# LED.net
KiCad netlist of a schematic drawn in Altium Designer
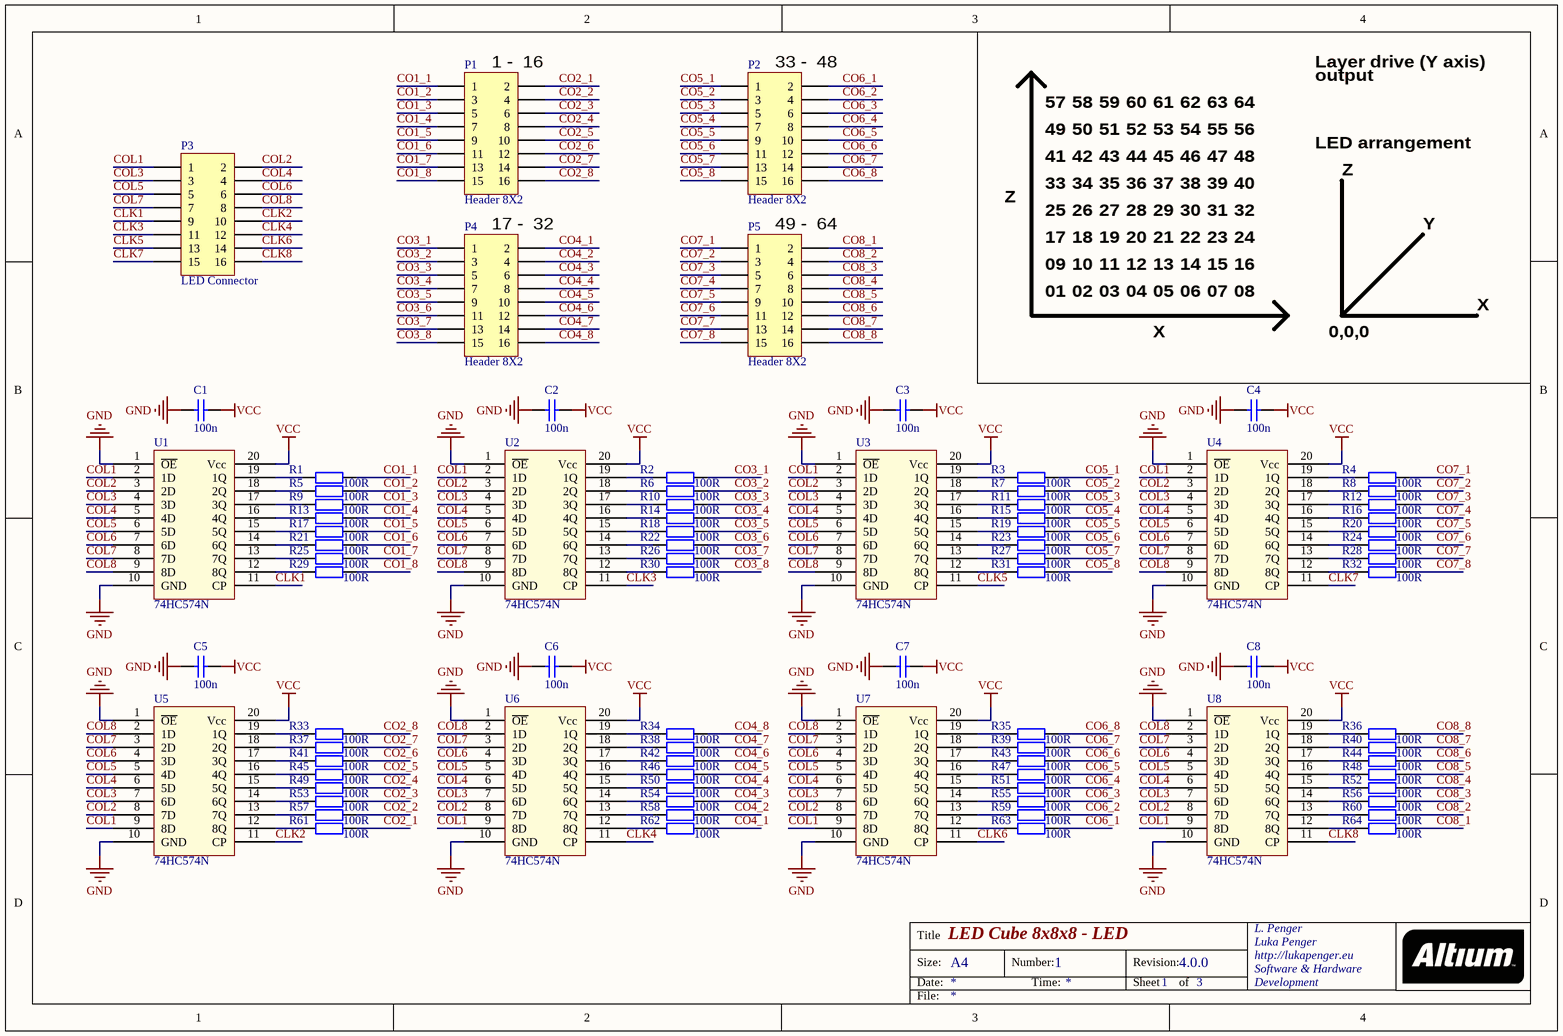
[diagram p0: LED.SchDoc]

(export (version "E")
  (design (tool "Eeschema 10.0.6"))
  (components
    (comp (ref "C1")
      (value "100n")
      (footprint "1608[0603]")
      (description "Capacitor")
      (fields (field (name "PUBLISHER") "Altium Limited"))
      (libsource (lib "Miscellaneous Devices") (part "Cap"))
    )
    (comp (ref "C2")
      (value "100n")
      (footprint "1608[0603]")
      (description "Capacitor")
      (fields (field (name "PUBLISHER") "Altium Limited"))
      (libsource (lib "Miscellaneous Devices") (part "Cap"))
    )
    (comp (ref "C3")
      (value "100n")
      (footprint "1608[0603]")
      (description "Capacitor")
      (fields (field (name "PUBLISHER") "Altium Limited"))
      (libsource (lib "Miscellaneous Devices") (part "Cap"))
    )
    (comp (ref "C4")
      (value "100n")
      (footprint "1608[0603]")
      (description "Capacitor")
      (fields (field (name "PUBLISHER") "Altium Limited"))
      (libsource (lib "Miscellaneous Devices") (part "Cap"))
    )
    (comp (ref "C5")
      (value "100n")
      (footprint "1608[0603]")
      (description "Capacitor")
      (fields (field (name "PUBLISHER") "Altium Limited"))
      (libsource (lib "Miscellaneous Devices") (part "Cap"))
    )
    (comp (ref "C6")
      (value "100n")
      (footprint "1608[0603]")
      (description "Capacitor")
      (fields (field (name "PUBLISHER") "Altium Limited"))
      (libsource (lib "Miscellaneous Devices") (part "Cap"))
    )
    (comp (ref "C7")
      (value "100n")
      (footprint "1608[0603]")
      (description "Capacitor")
      (fields (field (name "PUBLISHER") "Altium Limited"))
      (libsource (lib "Miscellaneous Devices") (part "Cap"))
    )
    (comp (ref "C8")
      (value "100n")
      (footprint "1608[0603]")
      (description "Capacitor")
      (fields (field (name "PUBLISHER") "Altium Limited"))
      (libsource (lib "Miscellaneous Devices") (part "Cap"))
    )
    (comp (ref "P1")
      (value "Header 8X2")
      (footprint "IDC-2x8")
      (description "Header, 8-Pin, Dual row")
      (fields (field (name "PUBLISHER") "Altium Limited"))
      (libsource (lib "Miscellaneous Connectors") (part "Header 8X2"))
    )
    (comp (ref "P2")
      (value "Header 8X2")
      (footprint "IDC-2x8")
      (description "Header, 8-Pin, Dual row")
      (fields (field (name "PUBLISHER") "Altium Limited"))
      (libsource (lib "Miscellaneous Connectors") (part "Header 8X2"))
    )
    (comp (ref "P3")
      (value "LED Connector")
      (footprint "IDC-2x8")
      (description "Header, 8-Pin, Dual row")
      (fields (field (name "PUBLISHER") "Altium Limited"))
      (libsource (lib "Miscellaneous Connectors") (part "Header 8X2"))
    )
    (comp (ref "P4")
      (value "Header 8X2")
      (footprint "IDC-2x8")
      (description "Header, 8-Pin, Dual row")
      (fields (field (name "PUBLISHER") "Altium Limited"))
      (libsource (lib "Miscellaneous Connectors") (part "Header 8X2"))
    )
    (comp (ref "P5")
      (value "Header 8X2")
      (footprint "IDC-2x8")
      (description "Header, 8-Pin, Dual row")
      (fields (field (name "PUBLISHER") "Altium Limited"))
      (libsource (lib "Miscellaneous Connectors") (part "Header 8X2"))
    )
    (comp (ref "R1")
      (value "100R")
      (footprint "C1206")
      (description "Resistor")
      (fields (field (name "PUBLISHER") "Altium Limited"))
      (libsource (lib "Miscellaneous Devices") (part "Res2"))
    )
    (comp (ref "R2")
      (value "100R")
      (footprint "C1206")
      (description "Resistor")
      (fields (field (name "PUBLISHER") "Altium Limited"))
      (libsource (lib "Miscellaneous Devices") (part "Res2"))
    )
    (comp (ref "R3")
      (value "100R")
      (footprint "C1206")
      (description "Resistor")
      (fields (field (name "PUBLISHER") "Altium Limited"))
      (libsource (lib "Miscellaneous Devices") (part "Res2"))
    )
    (comp (ref "R4")
      (value "100R")
      (footprint "C1206")
      (description "Resistor")
      (fields (field (name "PUBLISHER") "Altium Limited"))
      (libsource (lib "Miscellaneous Devices") (part "Res2"))
    )
    (comp (ref "R5")
      (value "100R")
      (footprint "C1206")
      (description "Resistor")
      (fields (field (name "PUBLISHER") "Altium Limited"))
      (libsource (lib "Miscellaneous Devices") (part "Res2"))
    )
    (comp (ref "R6")
      (value "100R")
      (footprint "C1206")
      (description "Resistor")
      (fields (field (name "PUBLISHER") "Altium Limited"))
      (libsource (lib "Miscellaneous Devices") (part "Res2"))
    )
    (comp (ref "R7")
      (value "100R")
      (footprint "C1206")
      (description "Resistor")
      (fields (field (name "PUBLISHER") "Altium Limited"))
      (libsource (lib "Miscellaneous Devices") (part "Res2"))
    )
    (comp (ref "R8")
      (value "100R")
      (footprint "C1206")
      (description "Resistor")
      (fields (field (name "PUBLISHER") "Altium Limited"))
      (libsource (lib "Miscellaneous Devices") (part "Res2"))
    )
    (comp (ref "R9")
      (value "100R")
      (footprint "C1206")
      (description "Resistor")
      (fields (field (name "PUBLISHER") "Altium Limited"))
      (libsource (lib "Miscellaneous Devices") (part "Res2"))
    )
    (comp (ref "R10")
      (value "100R")
      (footprint "C1206")
      (description "Resistor")
      (fields (field (name "PUBLISHER") "Altium Limited"))
      (libsource (lib "Miscellaneous Devices") (part "Res2"))
    )
    (comp (ref "R11")
      (value "100R")
      (footprint "C1206")
      (description "Resistor")
      (fields (field (name "PUBLISHER") "Altium Limited"))
      (libsource (lib "Miscellaneous Devices") (part "Res2"))
    )
    (comp (ref "R12")
      (value "100R")
      (footprint "C1206")
      (description "Resistor")
      (fields (field (name "PUBLISHER") "Altium Limited"))
      (libsource (lib "Miscellaneous Devices") (part "Res2"))
    )
    (comp (ref "R13")
      (value "100R")
      (footprint "C1206")
      (description "Resistor")
      (fields (field (name "PUBLISHER") "Altium Limited"))
      (libsource (lib "Miscellaneous Devices") (part "Res2"))
    )
    (comp (ref "R14")
      (value "100R")
      (footprint "C1206")
      (description "Resistor")
      (fields (field (name "PUBLISHER") "Altium Limited"))
      (libsource (lib "Miscellaneous Devices") (part "Res2"))
    )
    (comp (ref "R15")
      (value "100R")
      (footprint "C1206")
      (description "Resistor")
      (fields (field (name "PUBLISHER") "Altium Limited"))
      (libsource (lib "Miscellaneous Devices") (part "Res2"))
    )
    (comp (ref "R16")
      (value "100R")
      (footprint "C1206")
      (description "Resistor")
      (fields (field (name "PUBLISHER") "Altium Limited"))
      (libsource (lib "Miscellaneous Devices") (part "Res2"))
    )
    (comp (ref "R17")
      (value "100R")
      (footprint "C1206")
      (description "Resistor")
      (fields (field (name "PUBLISHER") "Altium Limited"))
      (libsource (lib "Miscellaneous Devices") (part "Res2"))
    )
    (comp (ref "R18")
      (value "100R")
      (footprint "C1206")
      (description "Resistor")
      (fields (field (name "PUBLISHER") "Altium Limited"))
      (libsource (lib "Miscellaneous Devices") (part "Res2"))
    )
    (comp (ref "R19")
      (value "100R")
      (footprint "C1206")
      (description "Resistor")
      (fields (field (name "PUBLISHER") "Altium Limited"))
      (libsource (lib "Miscellaneous Devices") (part "Res2"))
    )
    (comp (ref "R20")
      (value "100R")
      (footprint "C1206")
      (description "Resistor")
      (fields (field (name "PUBLISHER") "Altium Limited"))
      (libsource (lib "Miscellaneous Devices") (part "Res2"))
    )
    (comp (ref "R21")
      (value "100R")
      (footprint "C1206")
      (description "Resistor")
      (fields (field (name "PUBLISHER") "Altium Limited"))
      (libsource (lib "Miscellaneous Devices") (part "Res2"))
    )
    (comp (ref "R22")
      (value "100R")
      (footprint "C1206")
      (description "Resistor")
      (fields (field (name "PUBLISHER") "Altium Limited"))
      (libsource (lib "Miscellaneous Devices") (part "Res2"))
    )
    (comp (ref "R23")
      (value "100R")
      (footprint "C1206")
      (description "Resistor")
      (fields (field (name "PUBLISHER") "Altium Limited"))
      (libsource (lib "Miscellaneous Devices") (part "Res2"))
    )
    (comp (ref "R24")
      (value "100R")
      (footprint "C1206")
      (description "Resistor")
      (fields (field (name "PUBLISHER") "Altium Limited"))
      (libsource (lib "Miscellaneous Devices") (part "Res2"))
    )
    (comp (ref "R25")
      (value "100R")
      (footprint "C1206")
      (description "Resistor")
      (fields (field (name "PUBLISHER") "Altium Limited"))
      (libsource (lib "Miscellaneous Devices") (part "Res2"))
    )
    (comp (ref "R26")
      (value "100R")
      (footprint "C1206")
      (description "Resistor")
      (fields (field (name "PUBLISHER") "Altium Limited"))
      (libsource (lib "Miscellaneous Devices") (part "Res2"))
    )
    (comp (ref "R27")
      (value "100R")
      (footprint "C1206")
      (description "Resistor")
      (fields (field (name "PUBLISHER") "Altium Limited"))
      (libsource (lib "Miscellaneous Devices") (part "Res2"))
    )
    (comp (ref "R28")
      (value "100R")
      (footprint "C1206")
      (description "Resistor")
      (fields (field (name "PUBLISHER") "Altium Limited"))
      (libsource (lib "Miscellaneous Devices") (part "Res2"))
    )
    (comp (ref "R29")
      (value "100R")
      (footprint "C1206")
      (description "Resistor")
      (fields (field (name "PUBLISHER") "Altium Limited"))
      (libsource (lib "Miscellaneous Devices") (part "Res2"))
    )
    (comp (ref "R30")
      (value "100R")
      (footprint "C1206")
      (description "Resistor")
      (fields (field (name "PUBLISHER") "Altium Limited"))
      (libsource (lib "Miscellaneous Devices") (part "Res2"))
    )
    (comp (ref "R31")
      (value "100R")
      (footprint "C1206")
      (description "Resistor")
      (fields (field (name "PUBLISHER") "Altium Limited"))
      (libsource (lib "Miscellaneous Devices") (part "Res2"))
    )
    (comp (ref "R32")
      (value "100R")
      (footprint "C1206")
      (description "Resistor")
      (fields (field (name "PUBLISHER") "Altium Limited"))
      (libsource (lib "Miscellaneous Devices") (part "Res2"))
    )
    (comp (ref "R33")
      (value "100R")
      (footprint "C1206")
      (description "Resistor")
      (fields (field (name "PUBLISHER") "Altium Limited"))
      (libsource (lib "Miscellaneous Devices") (part "Res2"))
    )
    (comp (ref "R34")
      (value "100R")
      (footprint "C1206")
      (description "Resistor")
      (fields (field (name "PUBLISHER") "Altium Limited"))
      (libsource (lib "Miscellaneous Devices") (part "Res2"))
    )
    (comp (ref "R35")
      (value "100R")
      (footprint "C1206")
      (description "Resistor")
      (fields (field (name "PUBLISHER") "Altium Limited"))
      (libsource (lib "Miscellaneous Devices") (part "Res2"))
    )
    (comp (ref "R36")
      (value "100R")
      (footprint "C1206")
      (description "Resistor")
      (fields (field (name "PUBLISHER") "Altium Limited"))
      (libsource (lib "Miscellaneous Devices") (part "Res2"))
    )
    (comp (ref "R37")
      (value "100R")
      (footprint "C1206")
      (description "Resistor")
      (fields (field (name "PUBLISHER") "Altium Limited"))
      (libsource (lib "Miscellaneous Devices") (part "Res2"))
    )
    (comp (ref "R38")
      (value "100R")
      (footprint "C1206")
      (description "Resistor")
      (fields (field (name "PUBLISHER") "Altium Limited"))
      (libsource (lib "Miscellaneous Devices") (part "Res2"))
    )
    (comp (ref "R39")
      (value "100R")
      (footprint "C1206")
      (description "Resistor")
      (fields (field (name "PUBLISHER") "Altium Limited"))
      (libsource (lib "Miscellaneous Devices") (part "Res2"))
    )
    (comp (ref "R40")
      (value "100R")
      (footprint "C1206")
      (description "Resistor")
      (fields (field (name "PUBLISHER") "Altium Limited"))
      (libsource (lib "Miscellaneous Devices") (part "Res2"))
    )
    (comp (ref "R41")
      (value "100R")
      (footprint "C1206")
      (description "Resistor")
      (fields (field (name "PUBLISHER") "Altium Limited"))
      (libsource (lib "Miscellaneous Devices") (part "Res2"))
    )
    (comp (ref "R42")
      (value "100R")
      (footprint "C1206")
      (description "Resistor")
      (fields (field (name "PUBLISHER") "Altium Limited"))
      (libsource (lib "Miscellaneous Devices") (part "Res2"))
    )
    (comp (ref "R43")
      (value "100R")
      (footprint "C1206")
      (description "Resistor")
      (fields (field (name "PUBLISHER") "Altium Limited"))
      (libsource (lib "Miscellaneous Devices") (part "Res2"))
    )
    (comp (ref "R44")
      (value "100R")
      (footprint "C1206")
      (description "Resistor")
      (fields (field (name "PUBLISHER") "Altium Limited"))
      (libsource (lib "Miscellaneous Devices") (part "Res2"))
    )
    (comp (ref "R45")
      (value "100R")
      (footprint "C1206")
      (description "Resistor")
      (fields (field (name "PUBLISHER") "Altium Limited"))
      (libsource (lib "Miscellaneous Devices") (part "Res2"))
    )
    (comp (ref "R46")
      (value "100R")
      (footprint "C1206")
      (description "Resistor")
      (fields (field (name "PUBLISHER") "Altium Limited"))
      (libsource (lib "Miscellaneous Devices") (part "Res2"))
    )
    (comp (ref "R47")
      (value "100R")
      (footprint "C1206")
      (description "Resistor")
      (fields (field (name "PUBLISHER") "Altium Limited"))
      (libsource (lib "Miscellaneous Devices") (part "Res2"))
    )
    (comp (ref "R48")
      (value "100R")
      (footprint "C1206")
      (description "Resistor")
      (fields (field (name "PUBLISHER") "Altium Limited"))
      (libsource (lib "Miscellaneous Devices") (part "Res2"))
    )
    (comp (ref "R49")
      (value "100R")
      (footprint "C1206")
      (description "Resistor")
      (fields (field (name "PUBLISHER") "Altium Limited"))
      (libsource (lib "Miscellaneous Devices") (part "Res2"))
    )
    (comp (ref "R50")
      (value "100R")
      (footprint "C1206")
      (description "Resistor")
      (fields (field (name "PUBLISHER") "Altium Limited"))
      (libsource (lib "Miscellaneous Devices") (part "Res2"))
    )
    (comp (ref "R51")
      (value "100R")
      (footprint "C1206")
      (description "Resistor")
      (fields (field (name "PUBLISHER") "Altium Limited"))
      (libsource (lib "Miscellaneous Devices") (part "Res2"))
    )
    (comp (ref "R52")
      (value "100R")
      (footprint "C1206")
      (description "Resistor")
      (fields (field (name "PUBLISHER") "Altium Limited"))
      (libsource (lib "Miscellaneous Devices") (part "Res2"))
    )
    (comp (ref "R53")
      (value "100R")
      (footprint "C1206")
      (description "Resistor")
      (fields (field (name "PUBLISHER") "Altium Limited"))
      (libsource (lib "Miscellaneous Devices") (part "Res2"))
    )
    (comp (ref "R54")
      (value "100R")
      (footprint "C1206")
      (description "Resistor")
      (fields (field (name "PUBLISHER") "Altium Limited"))
      (libsource (lib "Miscellaneous Devices") (part "Res2"))
    )
    (comp (ref "R55")
      (value "100R")
      (footprint "C1206")
      (description "Resistor")
      (fields (field (name "PUBLISHER") "Altium Limited"))
      (libsource (lib "Miscellaneous Devices") (part "Res2"))
    )
    (comp (ref "R56")
      (value "100R")
      (footprint "C1206")
      (description "Resistor")
      (fields (field (name "PUBLISHER") "Altium Limited"))
      (libsource (lib "Miscellaneous Devices") (part "Res2"))
    )
    (comp (ref "R57")
      (value "100R")
      (footprint "C1206")
      (description "Resistor")
      (fields (field (name "PUBLISHER") "Altium Limited"))
      (libsource (lib "Miscellaneous Devices") (part "Res2"))
    )
    (comp (ref "R58")
      (value "100R")
      (footprint "C1206")
      (description "Resistor")
      (fields (field (name "PUBLISHER") "Altium Limited"))
      (libsource (lib "Miscellaneous Devices") (part "Res2"))
    )
    (comp (ref "R59")
      (value "100R")
      (footprint "C1206")
      (description "Resistor")
      (fields (field (name "PUBLISHER") "Altium Limited"))
      (libsource (lib "Miscellaneous Devices") (part "Res2"))
    )
    (comp (ref "R60")
      (value "100R")
      (footprint "C1206")
      (description "Resistor")
      (fields (field (name "PUBLISHER") "Altium Limited"))
      (libsource (lib "Miscellaneous Devices") (part "Res2"))
    )
    (comp (ref "R61")
      (value "100R")
      (footprint "C1206")
      (description "Resistor")
      (fields (field (name "PUBLISHER") "Altium Limited"))
      (libsource (lib "Miscellaneous Devices") (part "Res2"))
    )
    (comp (ref "R62")
      (value "100R")
      (footprint "C1206")
      (description "Resistor")
      (fields (field (name "PUBLISHER") "Altium Limited"))
      (libsource (lib "Miscellaneous Devices") (part "Res2"))
    )
    (comp (ref "R63")
      (value "100R")
      (footprint "C1206")
      (description "Resistor")
      (fields (field (name "PUBLISHER") "Altium Limited"))
      (libsource (lib "Miscellaneous Devices") (part "Res2"))
    )
    (comp (ref "R64")
      (value "100R")
      (footprint "C1206")
      (description "Resistor")
      (fields (field (name "PUBLISHER") "Altium Limited"))
      (libsource (lib "Miscellaneous Devices") (part "Res2"))
    )
    (comp (ref "U1")
      (value "74HC574N")
      (footprint "DIP20")
      (description "D Flip Flops")
      (libsource (lib "LukaLIBRARY") (part "74HCT574"))
    )
    (comp (ref "U2")
      (value "74HC574N")
      (footprint "DIP20")
      (description "D Flip Flops")
      (libsource (lib "LukaLIBRARY") (part "74HCT574"))
    )
    (comp (ref "U3")
      (value "74HC574N")
      (footprint "DIP20")
      (description "D Flip Flops")
      (libsource (lib "LukaLIBRARY") (part "74HCT574"))
    )
    (comp (ref "U4")
      (value "74HC574N")
      (footprint "DIP20")
      (description "D Flip Flops")
      (libsource (lib "LukaLIBRARY") (part "74HCT574"))
    )
    (comp (ref "U5")
      (value "74HC574N")
      (footprint "DIP20")
      (description "D Flip Flops")
      (libsource (lib "LukaLIBRARY") (part "74HCT574"))
    )
    (comp (ref "U6")
      (value "74HC574N")
      (footprint "DIP20")
      (description "D Flip Flops")
      (libsource (lib "LukaLIBRARY") (part "74HCT574"))
    )
    (comp (ref "U7")
      (value "74HC574N")
      (footprint "DIP20")
      (description "D Flip Flops")
      (libsource (lib "LukaLIBRARY") (part "74HCT574"))
    )
    (comp (ref "U8")
      (value "74HC574N")
      (footprint "DIP20")
      (description "D Flip Flops")
      (libsource (lib "LukaLIBRARY") (part "74HCT574"))
    )
  )
  (nets
    (net (code "1") (name "/CLK1") (class "Default")
      (node (ref "P3") (pin "9") (pinfunction "9_9") (pintype "passive"))
      (node (ref "U1") (pin "11") (pinfunction "CP_11") (pintype "passive"))
    )
    (net (code "2") (name "/CLK2") (class "Default")
      (node (ref "P3") (pin "10") (pinfunction "10_10") (pintype "passive"))
      (node (ref "U5") (pin "11") (pinfunction "CP_11") (pintype "passive"))
    )
    (net (code "3") (name "/CLK3") (class "Default")
      (node (ref "P3") (pin "11") (pinfunction "11_11") (pintype "passive"))
      (node (ref "U2") (pin "11") (pinfunction "CP_11") (pintype "passive"))
    )
    (net (code "4") (name "/CLK4") (class "Default")
      (node (ref "P3") (pin "12") (pinfunction "12_12") (pintype "passive"))
      (node (ref "U6") (pin "11") (pinfunction "CP_11") (pintype "passive"))
    )
    (net (code "5") (name "/CLK5") (class "Default")
      (node (ref "P3") (pin "13") (pinfunction "13_13") (pintype "passive"))
      (node (ref "U3") (pin "11") (pinfunction "CP_11") (pintype "passive"))
    )
    (net (code "6") (name "/CLK6") (class "Default")
      (node (ref "P3") (pin "14") (pinfunction "14_14") (pintype "passive"))
      (node (ref "U7") (pin "11") (pinfunction "CP_11") (pintype "passive"))
    )
    (net (code "7") (name "/CLK7") (class "Default")
      (node (ref "P3") (pin "15") (pinfunction "15_15") (pintype "passive"))
      (node (ref "U4") (pin "11") (pinfunction "CP_11") (pintype "passive"))
    )
    (net (code "8") (name "/CLK8") (class "Default")
      (node (ref "P3") (pin "16") (pinfunction "16_16") (pintype "passive"))
      (node (ref "U8") (pin "11") (pinfunction "CP_11") (pintype "passive"))
    )
    (net (code "9") (name "/CO1_1") (class "Default")
      (node (ref "P1") (pin "1") (pinfunction "1_1") (pintype "passive"))
      (node (ref "R1") (pin "2") (pinfunction "2_2") (pintype "passive"))
    )
    (net (code "10") (name "/CO1_2") (class "Default")
      (node (ref "P1") (pin "3") (pinfunction "3_3") (pintype "passive"))
      (node (ref "R5") (pin "2") (pinfunction "2_2") (pintype "passive"))
    )
    (net (code "11") (name "/CO1_3") (class "Default")
      (node (ref "P1") (pin "5") (pinfunction "5_5") (pintype "passive"))
      (node (ref "R9") (pin "2") (pinfunction "2_2") (pintype "passive"))
    )
    (net (code "12") (name "/CO1_4") (class "Default")
      (node (ref "P1") (pin "7") (pinfunction "7_7") (pintype "passive"))
      (node (ref "R13") (pin "2") (pinfunction "2_2") (pintype "passive"))
    )
    (net (code "13") (name "/CO1_5") (class "Default")
      (node (ref "P1") (pin "9") (pinfunction "9_9") (pintype "passive"))
      (node (ref "R17") (pin "2") (pinfunction "2_2") (pintype "passive"))
    )
    (net (code "14") (name "/CO1_6") (class "Default")
      (node (ref "P1") (pin "11") (pinfunction "11_11") (pintype "passive"))
      (node (ref "R21") (pin "2") (pinfunction "2_2") (pintype "passive"))
    )
    (net (code "15") (name "/CO1_7") (class "Default")
      (node (ref "P1") (pin "13") (pinfunction "13_13") (pintype "passive"))
      (node (ref "R25") (pin "2") (pinfunction "2_2") (pintype "passive"))
    )
    (net (code "16") (name "/CO1_8") (class "Default")
      (node (ref "P1") (pin "15") (pinfunction "15_15") (pintype "passive"))
      (node (ref "R29") (pin "2") (pinfunction "2_2") (pintype "passive"))
    )
    (net (code "17") (name "/CO2_1") (class "Default")
      (node (ref "P1") (pin "2") (pinfunction "2_2") (pintype "passive"))
      (node (ref "R61") (pin "2") (pinfunction "2_2") (pintype "passive"))
    )
    (net (code "18") (name "/CO2_2") (class "Default")
      (node (ref "P1") (pin "4") (pinfunction "4_4") (pintype "passive"))
      (node (ref "R57") (pin "2") (pinfunction "2_2") (pintype "passive"))
    )
    (net (code "19") (name "/CO2_3") (class "Default")
      (node (ref "P1") (pin "6") (pinfunction "6_6") (pintype "passive"))
      (node (ref "R53") (pin "2") (pinfunction "2_2") (pintype "passive"))
    )
    (net (code "20") (name "/CO2_4") (class "Default")
      (node (ref "P1") (pin "8") (pinfunction "8_8") (pintype "passive"))
      (node (ref "R49") (pin "2") (pinfunction "2_2") (pintype "passive"))
    )
    (net (code "21") (name "/CO2_5") (class "Default")
      (node (ref "P1") (pin "10") (pinfunction "10_10") (pintype "passive"))
      (node (ref "R45") (pin "2") (pinfunction "2_2") (pintype "passive"))
    )
    (net (code "22") (name "/CO2_6") (class "Default")
      (node (ref "P1") (pin "12") (pinfunction "12_12") (pintype "passive"))
      (node (ref "R41") (pin "2") (pinfunction "2_2") (pintype "passive"))
    )
    (net (code "23") (name "/CO2_7") (class "Default")
      (node (ref "P1") (pin "14") (pinfunction "14_14") (pintype "passive"))
      (node (ref "R37") (pin "2") (pinfunction "2_2") (pintype "passive"))
    )
    (net (code "24") (name "/CO2_8") (class "Default")
      (node (ref "P1") (pin "16") (pinfunction "16_16") (pintype "passive"))
      (node (ref "R33") (pin "2") (pinfunction "2_2") (pintype "passive"))
    )
    (net (code "25") (name "/CO3_1") (class "Default")
      (node (ref "P4") (pin "1") (pinfunction "1_1") (pintype "passive"))
      (node (ref "R2") (pin "2") (pinfunction "2_2") (pintype "passive"))
    )
    (net (code "26") (name "/CO3_2") (class "Default")
      (node (ref "P4") (pin "3") (pinfunction "3_3") (pintype "passive"))
      (node (ref "R6") (pin "2") (pinfunction "2_2") (pintype "passive"))
    )
    (net (code "27") (name "/CO3_3") (class "Default")
      (node (ref "P4") (pin "5") (pinfunction "5_5") (pintype "passive"))
      (node (ref "R10") (pin "2") (pinfunction "2_2") (pintype "passive"))
    )
    (net (code "28") (name "/CO3_4") (class "Default")
      (node (ref "P4") (pin "7") (pinfunction "7_7") (pintype "passive"))
      (node (ref "R14") (pin "2") (pinfunction "2_2") (pintype "passive"))
    )
    (net (code "29") (name "/CO3_5") (class "Default")
      (node (ref "P4") (pin "9") (pinfunction "9_9") (pintype "passive"))
      (node (ref "R18") (pin "2") (pinfunction "2_2") (pintype "passive"))
    )
    (net (code "30") (name "/CO3_6") (class "Default")
      (node (ref "P4") (pin "11") (pinfunction "11_11") (pintype "passive"))
      (node (ref "R22") (pin "2") (pinfunction "2_2") (pintype "passive"))
    )
    (net (code "31") (name "/CO3_7") (class "Default")
      (node (ref "P4") (pin "13") (pinfunction "13_13") (pintype "passive"))
      (node (ref "R26") (pin "2") (pinfunction "2_2") (pintype "passive"))
    )
    (net (code "32") (name "/CO3_8") (class "Default")
      (node (ref "P4") (pin "15") (pinfunction "15_15") (pintype "passive"))
      (node (ref "R30") (pin "2") (pinfunction "2_2") (pintype "passive"))
    )
    (net (code "33") (name "/CO4_1") (class "Default")
      (node (ref "P4") (pin "2") (pinfunction "2_2") (pintype "passive"))
      (node (ref "R62") (pin "2") (pinfunction "2_2") (pintype "passive"))
    )
    (net (code "34") (name "/CO4_2") (class "Default")
      (node (ref "P4") (pin "4") (pinfunction "4_4") (pintype "passive"))
      (node (ref "R58") (pin "2") (pinfunction "2_2") (pintype "passive"))
    )
    (net (code "35") (name "/CO4_3") (class "Default")
      (node (ref "P4") (pin "6") (pinfunction "6_6") (pintype "passive"))
      (node (ref "R54") (pin "2") (pinfunction "2_2") (pintype "passive"))
    )
    (net (code "36") (name "/CO4_4") (class "Default")
      (node (ref "P4") (pin "8") (pinfunction "8_8") (pintype "passive"))
      (node (ref "R50") (pin "2") (pinfunction "2_2") (pintype "passive"))
    )
    (net (code "37") (name "/CO4_5") (class "Default")
      (node (ref "P4") (pin "10") (pinfunction "10_10") (pintype "passive"))
      (node (ref "R46") (pin "2") (pinfunction "2_2") (pintype "passive"))
    )
    (net (code "38") (name "/CO4_6") (class "Default")
      (node (ref "P4") (pin "12") (pinfunction "12_12") (pintype "passive"))
      (node (ref "R42") (pin "2") (pinfunction "2_2") (pintype "passive"))
    )
    (net (code "39") (name "/CO4_7") (class "Default")
      (node (ref "P4") (pin "14") (pinfunction "14_14") (pintype "passive"))
      (node (ref "R38") (pin "2") (pinfunction "2_2") (pintype "passive"))
    )
    (net (code "40") (name "/CO4_8") (class "Default")
      (node (ref "P4") (pin "16") (pinfunction "16_16") (pintype "passive"))
      (node (ref "R34") (pin "2") (pinfunction "2_2") (pintype "passive"))
    )
    (net (code "41") (name "/CO5_1") (class "Default")
      (node (ref "P2") (pin "1") (pinfunction "1_1") (pintype "passive"))
      (node (ref "R3") (pin "2") (pinfunction "2_2") (pintype "passive"))
    )
    (net (code "42") (name "/CO5_2") (class "Default")
      (node (ref "P2") (pin "3") (pinfunction "3_3") (pintype "passive"))
      (node (ref "R7") (pin "2") (pinfunction "2_2") (pintype "passive"))
    )
    (net (code "43") (name "/CO5_3") (class "Default")
      (node (ref "P2") (pin "5") (pinfunction "5_5") (pintype "passive"))
      (node (ref "R11") (pin "2") (pinfunction "2_2") (pintype "passive"))
    )
    (net (code "44") (name "/CO5_4") (class "Default")
      (node (ref "P2") (pin "7") (pinfunction "7_7") (pintype "passive"))
      (node (ref "R15") (pin "2") (pinfunction "2_2") (pintype "passive"))
    )
    (net (code "45") (name "/CO5_5") (class "Default")
      (node (ref "P2") (pin "9") (pinfunction "9_9") (pintype "passive"))
      (node (ref "R19") (pin "2") (pinfunction "2_2") (pintype "passive"))
    )
    (net (code "46") (name "/CO5_6") (class "Default")
      (node (ref "P2") (pin "11") (pinfunction "11_11") (pintype "passive"))
      (node (ref "R23") (pin "2") (pinfunction "2_2") (pintype "passive"))
    )
    (net (code "47") (name "/CO5_7") (class "Default")
      (node (ref "P2") (pin "13") (pinfunction "13_13") (pintype "passive"))
      (node (ref "R27") (pin "2") (pinfunction "2_2") (pintype "passive"))
    )
    (net (code "48") (name "/CO5_8") (class "Default")
      (node (ref "P2") (pin "15") (pinfunction "15_15") (pintype "passive"))
      (node (ref "R31") (pin "2") (pinfunction "2_2") (pintype "passive"))
    )
    (net (code "49") (name "/CO6_1") (class "Default")
      (node (ref "P2") (pin "2") (pinfunction "2_2") (pintype "passive"))
      (node (ref "R63") (pin "2") (pinfunction "2_2") (pintype "passive"))
    )
    (net (code "50") (name "/CO6_2") (class "Default")
      (node (ref "P2") (pin "4") (pinfunction "4_4") (pintype "passive"))
      (node (ref "R59") (pin "2") (pinfunction "2_2") (pintype "passive"))
    )
    (net (code "51") (name "/CO6_3") (class "Default")
      (node (ref "P2") (pin "6") (pinfunction "6_6") (pintype "passive"))
      (node (ref "R55") (pin "2") (pinfunction "2_2") (pintype "passive"))
    )
    (net (code "52") (name "/CO6_4") (class "Default")
      (node (ref "P2") (pin "8") (pinfunction "8_8") (pintype "passive"))
      (node (ref "R51") (pin "2") (pinfunction "2_2") (pintype "passive"))
    )
    (net (code "53") (name "/CO6_5") (class "Default")
      (node (ref "P2") (pin "10") (pinfunction "10_10") (pintype "passive"))
      (node (ref "R47") (pin "2") (pinfunction "2_2") (pintype "passive"))
    )
    (net (code "54") (name "/CO6_6") (class "Default")
      (node (ref "P2") (pin "12") (pinfunction "12_12") (pintype "passive"))
      (node (ref "R43") (pin "2") (pinfunction "2_2") (pintype "passive"))
    )
    (net (code "55") (name "/CO6_7") (class "Default")
      (node (ref "P2") (pin "14") (pinfunction "14_14") (pintype "passive"))
      (node (ref "R39") (pin "2") (pinfunction "2_2") (pintype "passive"))
    )
    (net (code "56") (name "/CO6_8") (class "Default")
      (node (ref "P2") (pin "16") (pinfunction "16_16") (pintype "passive"))
      (node (ref "R35") (pin "2") (pinfunction "2_2") (pintype "passive"))
    )
    (net (code "57") (name "/CO7_1") (class "Default")
      (node (ref "P5") (pin "1") (pinfunction "1_1") (pintype "passive"))
      (node (ref "R4") (pin "2") (pinfunction "2_2") (pintype "passive"))
    )
    (net (code "58") (name "/CO7_2") (class "Default")
      (node (ref "P5") (pin "3") (pinfunction "3_3") (pintype "passive"))
      (node (ref "R8") (pin "2") (pinfunction "2_2") (pintype "passive"))
    )
    (net (code "59") (name "/CO7_3") (class "Default")
      (node (ref "P5") (pin "5") (pinfunction "5_5") (pintype "passive"))
      (node (ref "R12") (pin "2") (pinfunction "2_2") (pintype "passive"))
    )
    (net (code "60") (name "/CO7_4") (class "Default")
      (node (ref "P5") (pin "7") (pinfunction "7_7") (pintype "passive"))
      (node (ref "R16") (pin "2") (pinfunction "2_2") (pintype "passive"))
    )
    (net (code "61") (name "/CO7_5") (class "Default")
      (node (ref "P5") (pin "9") (pinfunction "9_9") (pintype "passive"))
      (node (ref "R20") (pin "2") (pinfunction "2_2") (pintype "passive"))
    )
    (net (code "62") (name "/CO7_6") (class "Default")
      (node (ref "P5") (pin "11") (pinfunction "11_11") (pintype "passive"))
      (node (ref "R24") (pin "2") (pinfunction "2_2") (pintype "passive"))
    )
    (net (code "63") (name "/CO7_7") (class "Default")
      (node (ref "P5") (pin "13") (pinfunction "13_13") (pintype "passive"))
      (node (ref "R28") (pin "2") (pinfunction "2_2") (pintype "passive"))
    )
    (net (code "64") (name "/CO7_8") (class "Default")
      (node (ref "P5") (pin "15") (pinfunction "15_15") (pintype "passive"))
      (node (ref "R32") (pin "2") (pinfunction "2_2") (pintype "passive"))
    )
    (net (code "65") (name "/CO8_1") (class "Default")
      (node (ref "P5") (pin "2") (pinfunction "2_2") (pintype "passive"))
      (node (ref "R64") (pin "2") (pinfunction "2_2") (pintype "passive"))
    )
    (net (code "66") (name "/CO8_2") (class "Default")
      (node (ref "P5") (pin "4") (pinfunction "4_4") (pintype "passive"))
      (node (ref "R60") (pin "2") (pinfunction "2_2") (pintype "passive"))
    )
    (net (code "67") (name "/CO8_3") (class "Default")
      (node (ref "P5") (pin "6") (pinfunction "6_6") (pintype "passive"))
      (node (ref "R56") (pin "2") (pinfunction "2_2") (pintype "passive"))
    )
    (net (code "68") (name "/CO8_4") (class "Default")
      (node (ref "P5") (pin "8") (pinfunction "8_8") (pintype "passive"))
      (node (ref "R52") (pin "2") (pinfunction "2_2") (pintype "passive"))
    )
    (net (code "69") (name "/CO8_5") (class "Default")
      (node (ref "P5") (pin "10") (pinfunction "10_10") (pintype "passive"))
      (node (ref "R48") (pin "2") (pinfunction "2_2") (pintype "passive"))
    )
    (net (code "70") (name "/CO8_6") (class "Default")
      (node (ref "P5") (pin "12") (pinfunction "12_12") (pintype "passive"))
      (node (ref "R44") (pin "2") (pinfunction "2_2") (pintype "passive"))
    )
    (net (code "71") (name "/CO8_7") (class "Default")
      (node (ref "P5") (pin "14") (pinfunction "14_14") (pintype "passive"))
      (node (ref "R40") (pin "2") (pinfunction "2_2") (pintype "passive"))
    )
    (net (code "72") (name "/CO8_8") (class "Default")
      (node (ref "P5") (pin "16") (pinfunction "16_16") (pintype "passive"))
      (node (ref "R36") (pin "2") (pinfunction "2_2") (pintype "passive"))
    )
    (net (code "73") (name "/COL1") (class "Default")
      (node (ref "P3") (pin "1") (pinfunction "1_1") (pintype "passive"))
      (node (ref "U1") (pin "2") (pinfunction "1D_2") (pintype "passive"))
      (node (ref "U2") (pin "2") (pinfunction "1D_2") (pintype "passive"))
      (node (ref "U3") (pin "2") (pinfunction "1D_2") (pintype "passive"))
      (node (ref "U4") (pin "2") (pinfunction "1D_2") (pintype "passive"))
      (node (ref "U5") (pin "9") (pinfunction "8D_9") (pintype "passive"))
      (node (ref "U6") (pin "9") (pinfunction "8D_9") (pintype "passive"))
      (node (ref "U7") (pin "9") (pinfunction "8D_9") (pintype "passive"))
      (node (ref "U8") (pin "9") (pinfunction "8D_9") (pintype "passive"))
    )
    (net (code "74") (name "/COL2") (class "Default")
      (node (ref "P3") (pin "2") (pinfunction "2_2") (pintype "passive"))
      (node (ref "U1") (pin "3") (pinfunction "2D_3") (pintype "passive"))
      (node (ref "U2") (pin "3") (pinfunction "2D_3") (pintype "passive"))
      (node (ref "U3") (pin "3") (pinfunction "2D_3") (pintype "passive"))
      (node (ref "U4") (pin "3") (pinfunction "2D_3") (pintype "passive"))
      (node (ref "U5") (pin "8") (pinfunction "7D_8") (pintype "passive"))
      (node (ref "U6") (pin "8") (pinfunction "7D_8") (pintype "passive"))
      (node (ref "U7") (pin "8") (pinfunction "7D_8") (pintype "passive"))
      (node (ref "U8") (pin "8") (pinfunction "7D_8") (pintype "passive"))
    )
    (net (code "75") (name "/COL3") (class "Default")
      (node (ref "P3") (pin "3") (pinfunction "3_3") (pintype "passive"))
      (node (ref "U1") (pin "4") (pinfunction "3D_4") (pintype "passive"))
      (node (ref "U2") (pin "4") (pinfunction "3D_4") (pintype "passive"))
      (node (ref "U3") (pin "4") (pinfunction "3D_4") (pintype "passive"))
      (node (ref "U4") (pin "4") (pinfunction "3D_4") (pintype "passive"))
      (node (ref "U5") (pin "7") (pinfunction "6D_7") (pintype "passive"))
      (node (ref "U6") (pin "7") (pinfunction "6D_7") (pintype "passive"))
      (node (ref "U7") (pin "7") (pinfunction "6D_7") (pintype "passive"))
      (node (ref "U8") (pin "7") (pinfunction "6D_7") (pintype "passive"))
    )
    (net (code "76") (name "/COL4") (class "Default")
      (node (ref "P3") (pin "4") (pinfunction "4_4") (pintype "passive"))
      (node (ref "U1") (pin "5") (pinfunction "4D_5") (pintype "passive"))
      (node (ref "U2") (pin "5") (pinfunction "4D_5") (pintype "passive"))
      (node (ref "U3") (pin "5") (pinfunction "4D_5") (pintype "passive"))
      (node (ref "U4") (pin "5") (pinfunction "4D_5") (pintype "passive"))
      (node (ref "U5") (pin "6") (pinfunction "5D_6") (pintype "passive"))
      (node (ref "U6") (pin "6") (pinfunction "5D_6") (pintype "passive"))
      (node (ref "U7") (pin "6") (pinfunction "5D_6") (pintype "passive"))
      (node (ref "U8") (pin "6") (pinfunction "5D_6") (pintype "passive"))
    )
    (net (code "77") (name "/COL5") (class "Default")
      (node (ref "P3") (pin "5") (pinfunction "5_5") (pintype "passive"))
      (node (ref "U1") (pin "6") (pinfunction "5D_6") (pintype "passive"))
      (node (ref "U2") (pin "6") (pinfunction "5D_6") (pintype "passive"))
      (node (ref "U3") (pin "6") (pinfunction "5D_6") (pintype "passive"))
      (node (ref "U4") (pin "6") (pinfunction "5D_6") (pintype "passive"))
      (node (ref "U5") (pin "5") (pinfunction "4D_5") (pintype "passive"))
      (node (ref "U6") (pin "5") (pinfunction "4D_5") (pintype "passive"))
      (node (ref "U7") (pin "5") (pinfunction "4D_5") (pintype "passive"))
      (node (ref "U8") (pin "5") (pinfunction "4D_5") (pintype "passive"))
    )
    (net (code "78") (name "/COL6") (class "Default")
      (node (ref "P3") (pin "6") (pinfunction "6_6") (pintype "passive"))
      (node (ref "U1") (pin "7") (pinfunction "6D_7") (pintype "passive"))
      (node (ref "U2") (pin "7") (pinfunction "6D_7") (pintype "passive"))
      (node (ref "U3") (pin "7") (pinfunction "6D_7") (pintype "passive"))
      (node (ref "U4") (pin "7") (pinfunction "6D_7") (pintype "passive"))
      (node (ref "U5") (pin "4") (pinfunction "3D_4") (pintype "passive"))
      (node (ref "U6") (pin "4") (pinfunction "3D_4") (pintype "passive"))
      (node (ref "U7") (pin "4") (pinfunction "3D_4") (pintype "passive"))
      (node (ref "U8") (pin "4") (pinfunction "3D_4") (pintype "passive"))
    )
    (net (code "79") (name "/COL7") (class "Default")
      (node (ref "P3") (pin "7") (pinfunction "7_7") (pintype "passive"))
      (node (ref "U1") (pin "8") (pinfunction "7D_8") (pintype "passive"))
      (node (ref "U2") (pin "8") (pinfunction "7D_8") (pintype "passive"))
      (node (ref "U3") (pin "8") (pinfunction "7D_8") (pintype "passive"))
      (node (ref "U4") (pin "8") (pinfunction "7D_8") (pintype "passive"))
      (node (ref "U5") (pin "3") (pinfunction "2D_3") (pintype "passive"))
      (node (ref "U6") (pin "3") (pinfunction "2D_3") (pintype "passive"))
      (node (ref "U7") (pin "3") (pinfunction "2D_3") (pintype "passive"))
      (node (ref "U8") (pin "3") (pinfunction "2D_3") (pintype "passive"))
    )
    (net (code "80") (name "/COL8") (class "Default")
      (node (ref "P3") (pin "8") (pinfunction "8_8") (pintype "passive"))
      (node (ref "U1") (pin "9") (pinfunction "8D_9") (pintype "passive"))
      (node (ref "U2") (pin "9") (pinfunction "8D_9") (pintype "passive"))
      (node (ref "U3") (pin "9") (pinfunction "8D_9") (pintype "passive"))
      (node (ref "U4") (pin "9") (pinfunction "8D_9") (pintype "passive"))
      (node (ref "U5") (pin "2") (pinfunction "1D_2") (pintype "passive"))
      (node (ref "U6") (pin "2") (pinfunction "1D_2") (pintype "passive"))
      (node (ref "U7") (pin "2") (pinfunction "1D_2") (pintype "passive"))
      (node (ref "U8") (pin "2") (pinfunction "1D_2") (pintype "passive"))
    )
    (net (code "81") (name "GND") (class "Default")
      (node (ref "C1") (pin "1") (pinfunction "1_1") (pintype "passive"))
      (node (ref "C2") (pin "1") (pinfunction "1_1") (pintype "passive"))
      (node (ref "C3") (pin "1") (pinfunction "1_1") (pintype "passive"))
      (node (ref "C4") (pin "1") (pinfunction "1_1") (pintype "passive"))
      (node (ref "C5") (pin "1") (pinfunction "1_1") (pintype "passive"))
      (node (ref "C6") (pin "1") (pinfunction "1_1") (pintype "passive"))
      (node (ref "C7") (pin "1") (pinfunction "1_1") (pintype "passive"))
      (node (ref "C8") (pin "1") (pinfunction "1_1") (pintype "passive"))
      (node (ref "U1") (pin "1") (pinfunction "~{OE}_1") (pintype "passive"))
      (node (ref "U1") (pin "10") (pinfunction "GND_10") (pintype "passive"))
      (node (ref "U2") (pin "1") (pinfunction "~{OE}_1") (pintype "passive"))
      (node (ref "U2") (pin "10") (pinfunction "GND_10") (pintype "passive"))
      (node (ref "U3") (pin "1") (pinfunction "~{OE}_1") (pintype "passive"))
      (node (ref "U3") (pin "10") (pinfunction "GND_10") (pintype "passive"))
      (node (ref "U4") (pin "1") (pinfunction "~{OE}_1") (pintype "passive"))
      (node (ref "U4") (pin "10") (pinfunction "GND_10") (pintype "passive"))
      (node (ref "U5") (pin "1") (pinfunction "~{OE}_1") (pintype "passive"))
      (node (ref "U5") (pin "10") (pinfunction "GND_10") (pintype "passive"))
      (node (ref "U6") (pin "1") (pinfunction "~{OE}_1") (pintype "passive"))
      (node (ref "U6") (pin "10") (pinfunction "GND_10") (pintype "passive"))
      (node (ref "U7") (pin "1") (pinfunction "~{OE}_1") (pintype "passive"))
      (node (ref "U7") (pin "10") (pinfunction "GND_10") (pintype "passive"))
      (node (ref "U8") (pin "1") (pinfunction "~{OE}_1") (pintype "passive"))
      (node (ref "U8") (pin "10") (pinfunction "GND_10") (pintype "passive"))
    )
    (net (code "82") (name "Net-(U1-1Q)") (class "Default")
      (node (ref "R1") (pin "1") (pinfunction "1_1") (pintype "passive"))
      (node (ref "U1") (pin "19") (pinfunction "1Q_19") (pintype "passive"))
    )
    (net (code "83") (name "Net-(U1-2Q)") (class "Default")
      (node (ref "R5") (pin "1") (pinfunction "1_1") (pintype "passive"))
      (node (ref "U1") (pin "18") (pinfunction "2Q_18") (pintype "passive"))
    )
    (net (code "84") (name "Net-(U1-3Q)") (class "Default")
      (node (ref "R9") (pin "1") (pinfunction "1_1") (pintype "passive"))
      (node (ref "U1") (pin "17") (pinfunction "3Q_17") (pintype "passive"))
    )
    (net (code "85") (name "Net-(U1-4Q)") (class "Default")
      (node (ref "R13") (pin "1") (pinfunction "1_1") (pintype "passive"))
      (node (ref "U1") (pin "16") (pinfunction "4Q_16") (pintype "passive"))
    )
    (net (code "86") (name "Net-(U1-5Q)") (class "Default")
      (node (ref "R17") (pin "1") (pinfunction "1_1") (pintype "passive"))
      (node (ref "U1") (pin "15") (pinfunction "5Q_15") (pintype "passive"))
    )
    (net (code "87") (name "Net-(U1-6Q)") (class "Default")
      (node (ref "R21") (pin "1") (pinfunction "1_1") (pintype "passive"))
      (node (ref "U1") (pin "14") (pinfunction "6Q_14") (pintype "passive"))
    )
    (net (code "88") (name "Net-(U1-7Q)") (class "Default")
      (node (ref "R25") (pin "1") (pinfunction "1_1") (pintype "passive"))
      (node (ref "U1") (pin "13") (pinfunction "7Q_13") (pintype "passive"))
    )
    (net (code "89") (name "Net-(U1-8Q)") (class "Default")
      (node (ref "R29") (pin "1") (pinfunction "1_1") (pintype "passive"))
      (node (ref "U1") (pin "12") (pinfunction "8Q_12") (pintype "passive"))
    )
    (net (code "90") (name "Net-(U2-1Q)") (class "Default")
      (node (ref "R2") (pin "1") (pinfunction "1_1") (pintype "passive"))
      (node (ref "U2") (pin "19") (pinfunction "1Q_19") (pintype "passive"))
    )
    (net (code "91") (name "Net-(U2-2Q)") (class "Default")
      (node (ref "R6") (pin "1") (pinfunction "1_1") (pintype "passive"))
      (node (ref "U2") (pin "18") (pinfunction "2Q_18") (pintype "passive"))
    )
    (net (code "92") (name "Net-(U2-3Q)") (class "Default")
      (node (ref "R10") (pin "1") (pinfunction "1_1") (pintype "passive"))
      (node (ref "U2") (pin "17") (pinfunction "3Q_17") (pintype "passive"))
    )
    (net (code "93") (name "Net-(U2-4Q)") (class "Default")
      (node (ref "R14") (pin "1") (pinfunction "1_1") (pintype "passive"))
      (node (ref "U2") (pin "16") (pinfunction "4Q_16") (pintype "passive"))
    )
    (net (code "94") (name "Net-(U2-5Q)") (class "Default")
      (node (ref "R18") (pin "1") (pinfunction "1_1") (pintype "passive"))
      (node (ref "U2") (pin "15") (pinfunction "5Q_15") (pintype "passive"))
    )
    (net (code "95") (name "Net-(U2-6Q)") (class "Default")
      (node (ref "R22") (pin "1") (pinfunction "1_1") (pintype "passive"))
      (node (ref "U2") (pin "14") (pinfunction "6Q_14") (pintype "passive"))
    )
    (net (code "96") (name "Net-(U2-7Q)") (class "Default")
      (node (ref "R26") (pin "1") (pinfunction "1_1") (pintype "passive"))
      (node (ref "U2") (pin "13") (pinfunction "7Q_13") (pintype "passive"))
    )
    (net (code "97") (name "Net-(U2-8Q)") (class "Default")
      (node (ref "R30") (pin "1") (pinfunction "1_1") (pintype "passive"))
      (node (ref "U2") (pin "12") (pinfunction "8Q_12") (pintype "passive"))
    )
    (net (code "98") (name "Net-(U3-1Q)") (class "Default")
      (node (ref "R3") (pin "1") (pinfunction "1_1") (pintype "passive"))
      (node (ref "U3") (pin "19") (pinfunction "1Q_19") (pintype "passive"))
    )
    (net (code "99") (name "Net-(U3-2Q)") (class "Default")
      (node (ref "R7") (pin "1") (pinfunction "1_1") (pintype "passive"))
      (node (ref "U3") (pin "18") (pinfunction "2Q_18") (pintype "passive"))
    )
    (net (code "100") (name "Net-(U3-3Q)") (class "Default")
      (node (ref "R11") (pin "1") (pinfunction "1_1") (pintype "passive"))
      (node (ref "U3") (pin "17") (pinfunction "3Q_17") (pintype "passive"))
    )
    (net (code "101") (name "Net-(U3-4Q)") (class "Default")
      (node (ref "R15") (pin "1") (pinfunction "1_1") (pintype "passive"))
      (node (ref "U3") (pin "16") (pinfunction "4Q_16") (pintype "passive"))
    )
    (net (code "102") (name "Net-(U3-5Q)") (class "Default")
      (node (ref "R19") (pin "1") (pinfunction "1_1") (pintype "passive"))
      (node (ref "U3") (pin "15") (pinfunction "5Q_15") (pintype "passive"))
    )
    (net (code "103") (name "Net-(U3-6Q)") (class "Default")
      (node (ref "R23") (pin "1") (pinfunction "1_1") (pintype "passive"))
      (node (ref "U3") (pin "14") (pinfunction "6Q_14") (pintype "passive"))
    )
    (net (code "104") (name "Net-(U3-7Q)") (class "Default")
      (node (ref "R27") (pin "1") (pinfunction "1_1") (pintype "passive"))
      (node (ref "U3") (pin "13") (pinfunction "7Q_13") (pintype "passive"))
    )
    (net (code "105") (name "Net-(U3-8Q)") (class "Default")
      (node (ref "R31") (pin "1") (pinfunction "1_1") (pintype "passive"))
      (node (ref "U3") (pin "12") (pinfunction "8Q_12") (pintype "passive"))
    )
    (net (code "106") (name "Net-(U4-1Q)") (class "Default")
      (node (ref "R4") (pin "1") (pinfunction "1_1") (pintype "passive"))
      (node (ref "U4") (pin "19") (pinfunction "1Q_19") (pintype "passive"))
    )
    (net (code "107") (name "Net-(U4-2Q)") (class "Default")
      (node (ref "R8") (pin "1") (pinfunction "1_1") (pintype "passive"))
      (node (ref "U4") (pin "18") (pinfunction "2Q_18") (pintype "passive"))
    )
    (net (code "108") (name "Net-(U4-3Q)") (class "Default")
      (node (ref "R12") (pin "1") (pinfunction "1_1") (pintype "passive"))
      (node (ref "U4") (pin "17") (pinfunction "3Q_17") (pintype "passive"))
    )
    (net (code "109") (name "Net-(U4-4Q)") (class "Default")
      (node (ref "R16") (pin "1") (pinfunction "1_1") (pintype "passive"))
      (node (ref "U4") (pin "16") (pinfunction "4Q_16") (pintype "passive"))
    )
    (net (code "110") (name "Net-(U4-5Q)") (class "Default")
      (node (ref "R20") (pin "1") (pinfunction "1_1") (pintype "passive"))
      (node (ref "U4") (pin "15") (pinfunction "5Q_15") (pintype "passive"))
    )
    (net (code "111") (name "Net-(U4-6Q)") (class "Default")
      (node (ref "R24") (pin "1") (pinfunction "1_1") (pintype "passive"))
      (node (ref "U4") (pin "14") (pinfunction "6Q_14") (pintype "passive"))
    )
    (net (code "112") (name "Net-(U4-7Q)") (class "Default")
      (node (ref "R28") (pin "1") (pinfunction "1_1") (pintype "passive"))
      (node (ref "U4") (pin "13") (pinfunction "7Q_13") (pintype "passive"))
    )
    (net (code "113") (name "Net-(U4-8Q)") (class "Default")
      (node (ref "R32") (pin "1") (pinfunction "1_1") (pintype "passive"))
      (node (ref "U4") (pin "12") (pinfunction "8Q_12") (pintype "passive"))
    )
    (net (code "114") (name "Net-(U5-1Q)") (class "Default")
      (node (ref "R33") (pin "1") (pinfunction "1_1") (pintype "passive"))
      (node (ref "U5") (pin "19") (pinfunction "1Q_19") (pintype "passive"))
    )
    (net (code "115") (name "Net-(U5-2Q)") (class "Default")
      (node (ref "R37") (pin "1") (pinfunction "1_1") (pintype "passive"))
      (node (ref "U5") (pin "18") (pinfunction "2Q_18") (pintype "passive"))
    )
    (net (code "116") (name "Net-(U5-3Q)") (class "Default")
      (node (ref "R41") (pin "1") (pinfunction "1_1") (pintype "passive"))
      (node (ref "U5") (pin "17") (pinfunction "3Q_17") (pintype "passive"))
    )
    (net (code "117") (name "Net-(U5-4Q)") (class "Default")
      (node (ref "R45") (pin "1") (pinfunction "1_1") (pintype "passive"))
      (node (ref "U5") (pin "16") (pinfunction "4Q_16") (pintype "passive"))
    )
    (net (code "118") (name "Net-(U5-5Q)") (class "Default")
      (node (ref "R49") (pin "1") (pinfunction "1_1") (pintype "passive"))
      (node (ref "U5") (pin "15") (pinfunction "5Q_15") (pintype "passive"))
    )
    (net (code "119") (name "Net-(U5-6Q)") (class "Default")
      (node (ref "R53") (pin "1") (pinfunction "1_1") (pintype "passive"))
      (node (ref "U5") (pin "14") (pinfunction "6Q_14") (pintype "passive"))
    )
    (net (code "120") (name "Net-(U5-7Q)") (class "Default")
      (node (ref "R57") (pin "1") (pinfunction "1_1") (pintype "passive"))
      (node (ref "U5") (pin "13") (pinfunction "7Q_13") (pintype "passive"))
    )
    (net (code "121") (name "Net-(U5-8Q)") (class "Default")
      (node (ref "R61") (pin "1") (pinfunction "1_1") (pintype "passive"))
      (node (ref "U5") (pin "12") (pinfunction "8Q_12") (pintype "passive"))
    )
    (net (code "122") (name "Net-(U6-1Q)") (class "Default")
      (node (ref "R34") (pin "1") (pinfunction "1_1") (pintype "passive"))
      (node (ref "U6") (pin "19") (pinfunction "1Q_19") (pintype "passive"))
    )
    (net (code "123") (name "Net-(U6-2Q)") (class "Default")
      (node (ref "R38") (pin "1") (pinfunction "1_1") (pintype "passive"))
      (node (ref "U6") (pin "18") (pinfunction "2Q_18") (pintype "passive"))
    )
    (net (code "124") (name "Net-(U6-3Q)") (class "Default")
      (node (ref "R42") (pin "1") (pinfunction "1_1") (pintype "passive"))
      (node (ref "U6") (pin "17") (pinfunction "3Q_17") (pintype "passive"))
    )
    (net (code "125") (name "Net-(U6-4Q)") (class "Default")
      (node (ref "R46") (pin "1") (pinfunction "1_1") (pintype "passive"))
      (node (ref "U6") (pin "16") (pinfunction "4Q_16") (pintype "passive"))
    )
    (net (code "126") (name "Net-(U6-5Q)") (class "Default")
      (node (ref "R50") (pin "1") (pinfunction "1_1") (pintype "passive"))
      (node (ref "U6") (pin "15") (pinfunction "5Q_15") (pintype "passive"))
    )
    (net (code "127") (name "Net-(U6-6Q)") (class "Default")
      (node (ref "R54") (pin "1") (pinfunction "1_1") (pintype "passive"))
      (node (ref "U6") (pin "14") (pinfunction "6Q_14") (pintype "passive"))
    )
    (net (code "128") (name "Net-(U6-7Q)") (class "Default")
      (node (ref "R58") (pin "1") (pinfunction "1_1") (pintype "passive"))
      (node (ref "U6") (pin "13") (pinfunction "7Q_13") (pintype "passive"))
    )
    (net (code "129") (name "Net-(U6-8Q)") (class "Default")
      (node (ref "R62") (pin "1") (pinfunction "1_1") (pintype "passive"))
      (node (ref "U6") (pin "12") (pinfunction "8Q_12") (pintype "passive"))
    )
    (net (code "130") (name "Net-(U7-1Q)") (class "Default")
      (node (ref "R35") (pin "1") (pinfunction "1_1") (pintype "passive"))
      (node (ref "U7") (pin "19") (pinfunction "1Q_19") (pintype "passive"))
    )
    (net (code "131") (name "Net-(U7-2Q)") (class "Default")
      (node (ref "R39") (pin "1") (pinfunction "1_1") (pintype "passive"))
      (node (ref "U7") (pin "18") (pinfunction "2Q_18") (pintype "passive"))
    )
    (net (code "132") (name "Net-(U7-3Q)") (class "Default")
      (node (ref "R43") (pin "1") (pinfunction "1_1") (pintype "passive"))
      (node (ref "U7") (pin "17") (pinfunction "3Q_17") (pintype "passive"))
    )
    (net (code "133") (name "Net-(U7-4Q)") (class "Default")
      (node (ref "R47") (pin "1") (pinfunction "1_1") (pintype "passive"))
      (node (ref "U7") (pin "16") (pinfunction "4Q_16") (pintype "passive"))
    )
    (net (code "134") (name "Net-(U7-5Q)") (class "Default")
      (node (ref "R51") (pin "1") (pinfunction "1_1") (pintype "passive"))
      (node (ref "U7") (pin "15") (pinfunction "5Q_15") (pintype "passive"))
    )
    (net (code "135") (name "Net-(U7-6Q)") (class "Default")
      (node (ref "R55") (pin "1") (pinfunction "1_1") (pintype "passive"))
      (node (ref "U7") (pin "14") (pinfunction "6Q_14") (pintype "passive"))
    )
    (net (code "136") (name "Net-(U7-7Q)") (class "Default")
      (node (ref "R59") (pin "1") (pinfunction "1_1") (pintype "passive"))
      (node (ref "U7") (pin "13") (pinfunction "7Q_13") (pintype "passive"))
    )
    (net (code "137") (name "Net-(U7-8Q)") (class "Default")
      (node (ref "R63") (pin "1") (pinfunction "1_1") (pintype "passive"))
      (node (ref "U7") (pin "12") (pinfunction "8Q_12") (pintype "passive"))
    )
    (net (code "138") (name "Net-(U8-1Q)") (class "Default")
      (node (ref "R36") (pin "1") (pinfunction "1_1") (pintype "passive"))
      (node (ref "U8") (pin "19") (pinfunction "1Q_19") (pintype "passive"))
    )
    (net (code "139") (name "Net-(U8-2Q)") (class "Default")
      (node (ref "R40") (pin "1") (pinfunction "1_1") (pintype "passive"))
      (node (ref "U8") (pin "18") (pinfunction "2Q_18") (pintype "passive"))
    )
    (net (code "140") (name "Net-(U8-3Q)") (class "Default")
      (node (ref "R44") (pin "1") (pinfunction "1_1") (pintype "passive"))
      (node (ref "U8") (pin "17") (pinfunction "3Q_17") (pintype "passive"))
    )
    (net (code "141") (name "Net-(U8-4Q)") (class "Default")
      (node (ref "R48") (pin "1") (pinfunction "1_1") (pintype "passive"))
      (node (ref "U8") (pin "16") (pinfunction "4Q_16") (pintype "passive"))
    )
    (net (code "142") (name "Net-(U8-5Q)") (class "Default")
      (node (ref "R52") (pin "1") (pinfunction "1_1") (pintype "passive"))
      (node (ref "U8") (pin "15") (pinfunction "5Q_15") (pintype "passive"))
    )
    (net (code "143") (name "Net-(U8-6Q)") (class "Default")
      (node (ref "R56") (pin "1") (pinfunction "1_1") (pintype "passive"))
      (node (ref "U8") (pin "14") (pinfunction "6Q_14") (pintype "passive"))
    )
    (net (code "144") (name "Net-(U8-7Q)") (class "Default")
      (node (ref "R60") (pin "1") (pinfunction "1_1") (pintype "passive"))
      (node (ref "U8") (pin "13") (pinfunction "7Q_13") (pintype "passive"))
    )
    (net (code "145") (name "Net-(U8-8Q)") (class "Default")
      (node (ref "R64") (pin "1") (pinfunction "1_1") (pintype "passive"))
      (node (ref "U8") (pin "12") (pinfunction "8Q_12") (pintype "passive"))
    )
    (net (code "146") (name "VCC") (class "Default")
      (node (ref "C1") (pin "2") (pinfunction "2_2") (pintype "passive"))
      (node (ref "C2") (pin "2") (pinfunction "2_2") (pintype "passive"))
      (node (ref "C3") (pin "2") (pinfunction "2_2") (pintype "passive"))
      (node (ref "C4") (pin "2") (pinfunction "2_2") (pintype "passive"))
      (node (ref "C5") (pin "2") (pinfunction "2_2") (pintype "passive"))
      (node (ref "C6") (pin "2") (pinfunction "2_2") (pintype "passive"))
      (node (ref "C7") (pin "2") (pinfunction "2_2") (pintype "passive"))
      (node (ref "C8") (pin "2") (pinfunction "2_2") (pintype "passive"))
      (node (ref "U1") (pin "20") (pinfunction "Vcc_20") (pintype "passive"))
      (node (ref "U2") (pin "20") (pinfunction "Vcc_20") (pintype "passive"))
      (node (ref "U3") (pin "20") (pinfunction "Vcc_20") (pintype "passive"))
      (node (ref "U4") (pin "20") (pinfunction "Vcc_20") (pintype "passive"))
      (node (ref "U5") (pin "20") (pinfunction "Vcc_20") (pintype "passive"))
      (node (ref "U6") (pin "20") (pinfunction "Vcc_20") (pintype "passive"))
      (node (ref "U7") (pin "20") (pinfunction "Vcc_20") (pintype "passive"))
      (node (ref "U8") (pin "20") (pinfunction "Vcc_20") (pintype "passive"))
    )
  )
)
